# microcontroller_r0.net
KiCad netlist of a schematic drawn in EAGLE
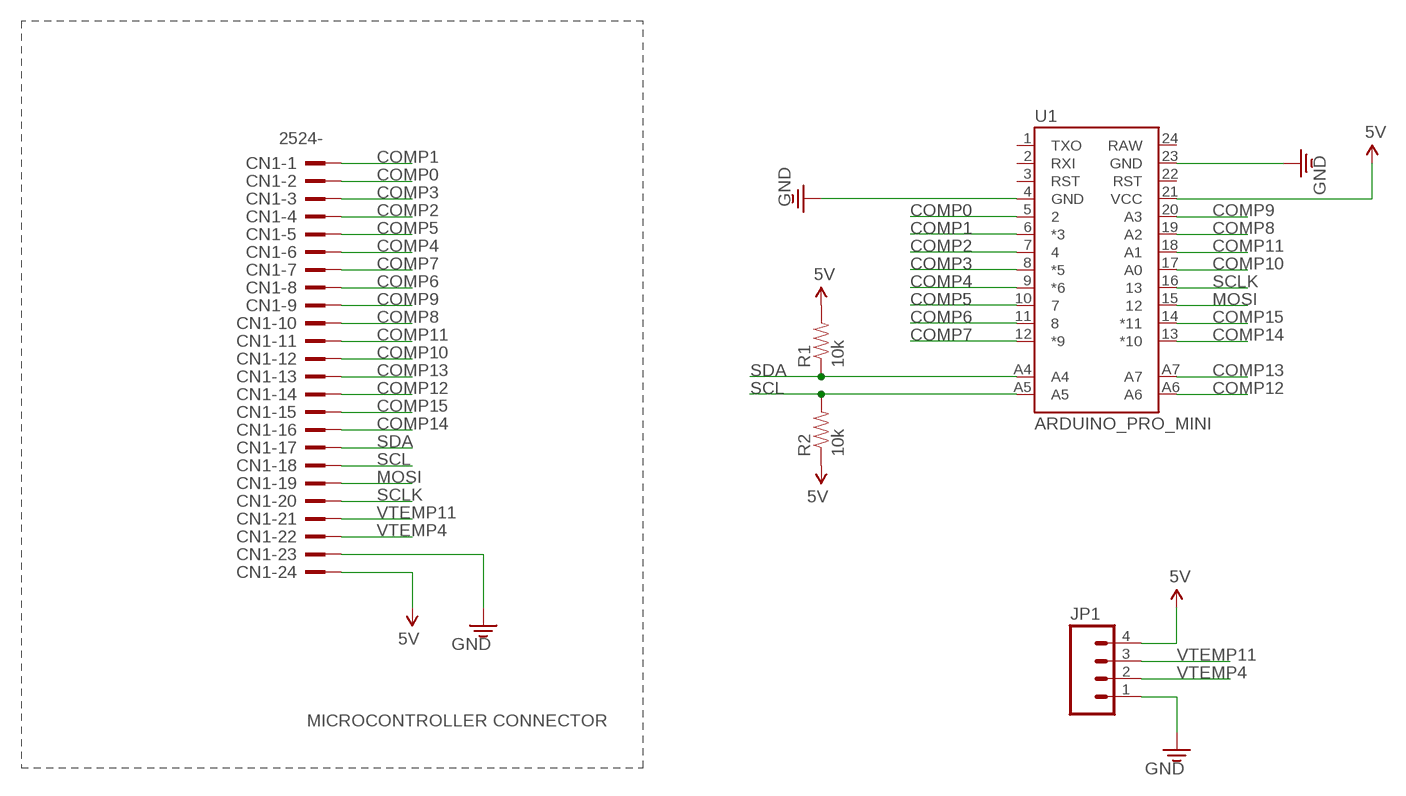
[diagram p0: schematic, sheet 1]

(export (version "E")
  (design (tool "Eeschema 10.0.6"))
  (components
    (comp (ref "CN1")
      (value "2524-")
      (footprint "eagle-import:PAK100_2500-24")
      (libsource (lib "eagle-import") (part "2524-"))
    )
    (comp (ref "JP1")
      (value "M04LOCK")
      (footprint "eagle-import:1X04_LOCK")
      (libsource (lib "eagle-import") (part "M04LOCK"))
    )
    (comp (ref "R1")
      (value "10k")
      (footprint "eagle-import:0603")
      (libsource (lib "eagle-import") (part "RESISTOR0603"))
    )
    (comp (ref "R2")
      (value "10k")
      (footprint "eagle-import:0603")
      (libsource (lib "eagle-import") (part "RESISTOR0603"))
    )
    (comp (ref "U1")
      (value "ARDUINO_PRO_MINI")
      (footprint "eagle-import:ARDUINO_PRO_MINI")
      (libsource (lib "eagle-import") (part "ARDUINO_PRO_MINI"))
    )
  )
  (nets
    (net (code "1") (name "/COMP0") (class "Default")
      (node (ref "CN1") (pin "2") (pinfunction "KL_2") (pintype "passive"))
      (node (ref "U1") (pin "5") (pinfunction "2_5") (pintype "bidirectional"))
    )
    (net (code "2") (name "/COMP1") (class "Default")
      (node (ref "CN1") (pin "1") (pinfunction "KL_1") (pintype "passive"))
      (node (ref "U1") (pin "6") (pinfunction "*3_6") (pintype "bidirectional"))
    )
    (net (code "3") (name "/COMP2") (class "Default")
      (node (ref "CN1") (pin "4") (pinfunction "KL_4") (pintype "passive"))
      (node (ref "U1") (pin "7") (pinfunction "4_7") (pintype "bidirectional"))
    )
    (net (code "4") (name "/COMP3") (class "Default")
      (node (ref "CN1") (pin "3") (pinfunction "KL_3") (pintype "passive"))
      (node (ref "U1") (pin "8") (pinfunction "*5_8") (pintype "bidirectional"))
    )
    (net (code "5") (name "/COMP4") (class "Default")
      (node (ref "CN1") (pin "6") (pinfunction "KL_6") (pintype "passive"))
      (node (ref "U1") (pin "9") (pinfunction "*6_9") (pintype "bidirectional"))
    )
    (net (code "6") (name "/COMP5") (class "Default")
      (node (ref "CN1") (pin "5") (pinfunction "KL_5") (pintype "passive"))
      (node (ref "U1") (pin "10") (pinfunction "7_10") (pintype "bidirectional"))
    )
    (net (code "7") (name "/COMP6") (class "Default")
      (node (ref "CN1") (pin "8") (pinfunction "KL_8") (pintype "passive"))
      (node (ref "U1") (pin "11") (pinfunction "8_11") (pintype "bidirectional"))
    )
    (net (code "8") (name "/COMP7") (class "Default")
      (node (ref "CN1") (pin "7") (pinfunction "KL_7") (pintype "passive"))
      (node (ref "U1") (pin "12") (pinfunction "*9_12") (pintype "bidirectional"))
    )
    (net (code "9") (name "/COMP8") (class "Default")
      (node (ref "CN1") (pin "10") (pinfunction "KL_10") (pintype "passive"))
      (node (ref "U1") (pin "19") (pinfunction "A2_19") (pintype "bidirectional"))
    )
    (net (code "10") (name "/COMP9") (class "Default")
      (node (ref "CN1") (pin "9") (pinfunction "KL_9") (pintype "passive"))
      (node (ref "U1") (pin "20") (pinfunction "A3_20") (pintype "bidirectional"))
    )
    (net (code "11") (name "/COMP10") (class "Default")
      (node (ref "CN1") (pin "12") (pinfunction "KL_12") (pintype "passive"))
      (node (ref "U1") (pin "17") (pinfunction "A0_17") (pintype "bidirectional"))
    )
    (net (code "12") (name "/COMP11") (class "Default")
      (node (ref "CN1") (pin "11") (pinfunction "KL_11") (pintype "passive"))
      (node (ref "U1") (pin "18") (pinfunction "A1_18") (pintype "bidirectional"))
    )
    (net (code "13") (name "/COMP12") (class "Default")
      (node (ref "CN1") (pin "14") (pinfunction "KL_14") (pintype "passive"))
      (node (ref "U1") (pin "A6") (pinfunction "A6_A6") (pintype "bidirectional"))
    )
    (net (code "14") (name "/COMP13") (class "Default")
      (node (ref "CN1") (pin "13") (pinfunction "KL_13") (pintype "passive"))
      (node (ref "U1") (pin "A7") (pinfunction "A7_A7") (pintype "bidirectional"))
    )
    (net (code "15") (name "/COMP14") (class "Default")
      (node (ref "CN1") (pin "16") (pinfunction "KL_16") (pintype "passive"))
      (node (ref "U1") (pin "13") (pinfunction "*10_13") (pintype "bidirectional"))
    )
    (net (code "16") (name "/COMP15") (class "Default")
      (node (ref "CN1") (pin "15") (pinfunction "KL_15") (pintype "passive"))
      (node (ref "U1") (pin "14") (pinfunction "*11_14") (pintype "bidirectional"))
    )
    (net (code "17") (name "/MOSI") (class "Default")
      (node (ref "CN1") (pin "19") (pinfunction "KL_19") (pintype "passive"))
      (node (ref "U1") (pin "15") (pinfunction "12_15") (pintype "bidirectional"))
    )
    (net (code "18") (name "/SCL") (class "Default")
      (node (ref "CN1") (pin "18") (pinfunction "KL_18") (pintype "passive"))
      (node (ref "R2") (pin "2") (pinfunction "2_2") (pintype "passive"))
      (node (ref "U1") (pin "A5") (pinfunction "A5_A5") (pintype "bidirectional"))
    )
    (net (code "19") (name "/SCLK") (class "Default")
      (node (ref "CN1") (pin "20") (pinfunction "KL_20") (pintype "passive"))
      (node (ref "U1") (pin "16") (pinfunction "13_16") (pintype "bidirectional"))
    )
    (net (code "20") (name "/SDA") (class "Default")
      (node (ref "CN1") (pin "17") (pinfunction "KL_17") (pintype "passive"))
      (node (ref "R1") (pin "1") (pinfunction "1_1") (pintype "passive"))
      (node (ref "U1") (pin "A4") (pinfunction "A4_A4") (pintype "bidirectional"))
    )
    (net (code "21") (name "/VTEMP4") (class "Default")
      (node (ref "CN1") (pin "22") (pinfunction "KL_22") (pintype "passive"))
      (node (ref "JP1") (pin "2") (pinfunction "2_2") (pintype "passive"))
    )
    (net (code "22") (name "/VTEMP11") (class "Default")
      (node (ref "CN1") (pin "21") (pinfunction "KL_21") (pintype "passive"))
      (node (ref "JP1") (pin "3") (pinfunction "3_3") (pintype "passive"))
    )
    (net (code "23") (name "5V") (class "Default")
      (node (ref "CN1") (pin "24") (pinfunction "KL_24") (pintype "passive"))
      (node (ref "JP1") (pin "4") (pinfunction "4_4") (pintype "passive"))
      (node (ref "R1") (pin "2") (pinfunction "2_2") (pintype "passive"))
      (node (ref "R2") (pin "1") (pinfunction "1_1") (pintype "passive"))
      (node (ref "U1") (pin "21") (pinfunction "VCC_21") (pintype "bidirectional"))
    )
    (net (code "24") (name "GND") (class "Default")
      (node (ref "CN1") (pin "23") (pinfunction "KL_23") (pintype "passive"))
      (node (ref "JP1") (pin "1") (pinfunction "1_1") (pintype "passive"))
      (node (ref "U1") (pin "23") (pinfunction "GND_23") (pintype "bidirectional"))
      (node (ref "U1") (pin "4") (pinfunction "GND_4") (pintype "bidirectional"))
    )
    (net (code "25") (name "unconnected-(U1-RAW-Pad24)") (class "Default")
      (node (ref "U1") (pin "24") (pinfunction "RAW_24") (pintype "bidirectional"))
    )
    (net (code "26") (name "unconnected-(U1-RST-Pad3)") (class "Default")
      (node (ref "U1") (pin "3") (pinfunction "RST_3") (pintype "bidirectional"))
    )
    (net (code "27") (name "unconnected-(U1-RST-Pad22)") (class "Default")
      (node (ref "U1") (pin "22") (pinfunction "RST_22") (pintype "bidirectional"))
    )
    (net (code "28") (name "unconnected-(U1-RXI-Pad2)") (class "Default")
      (node (ref "U1") (pin "2") (pinfunction "RXI_2") (pintype "bidirectional"))
    )
    (net (code "29") (name "unconnected-(U1-TXO-Pad1)") (class "Default")
      (node (ref "U1") (pin "1") (pinfunction "TXO_1") (pintype "bidirectional"))
    )
  )
)
